# Schematic.net
KiCad netlist of a schematic drawn in EAGLE
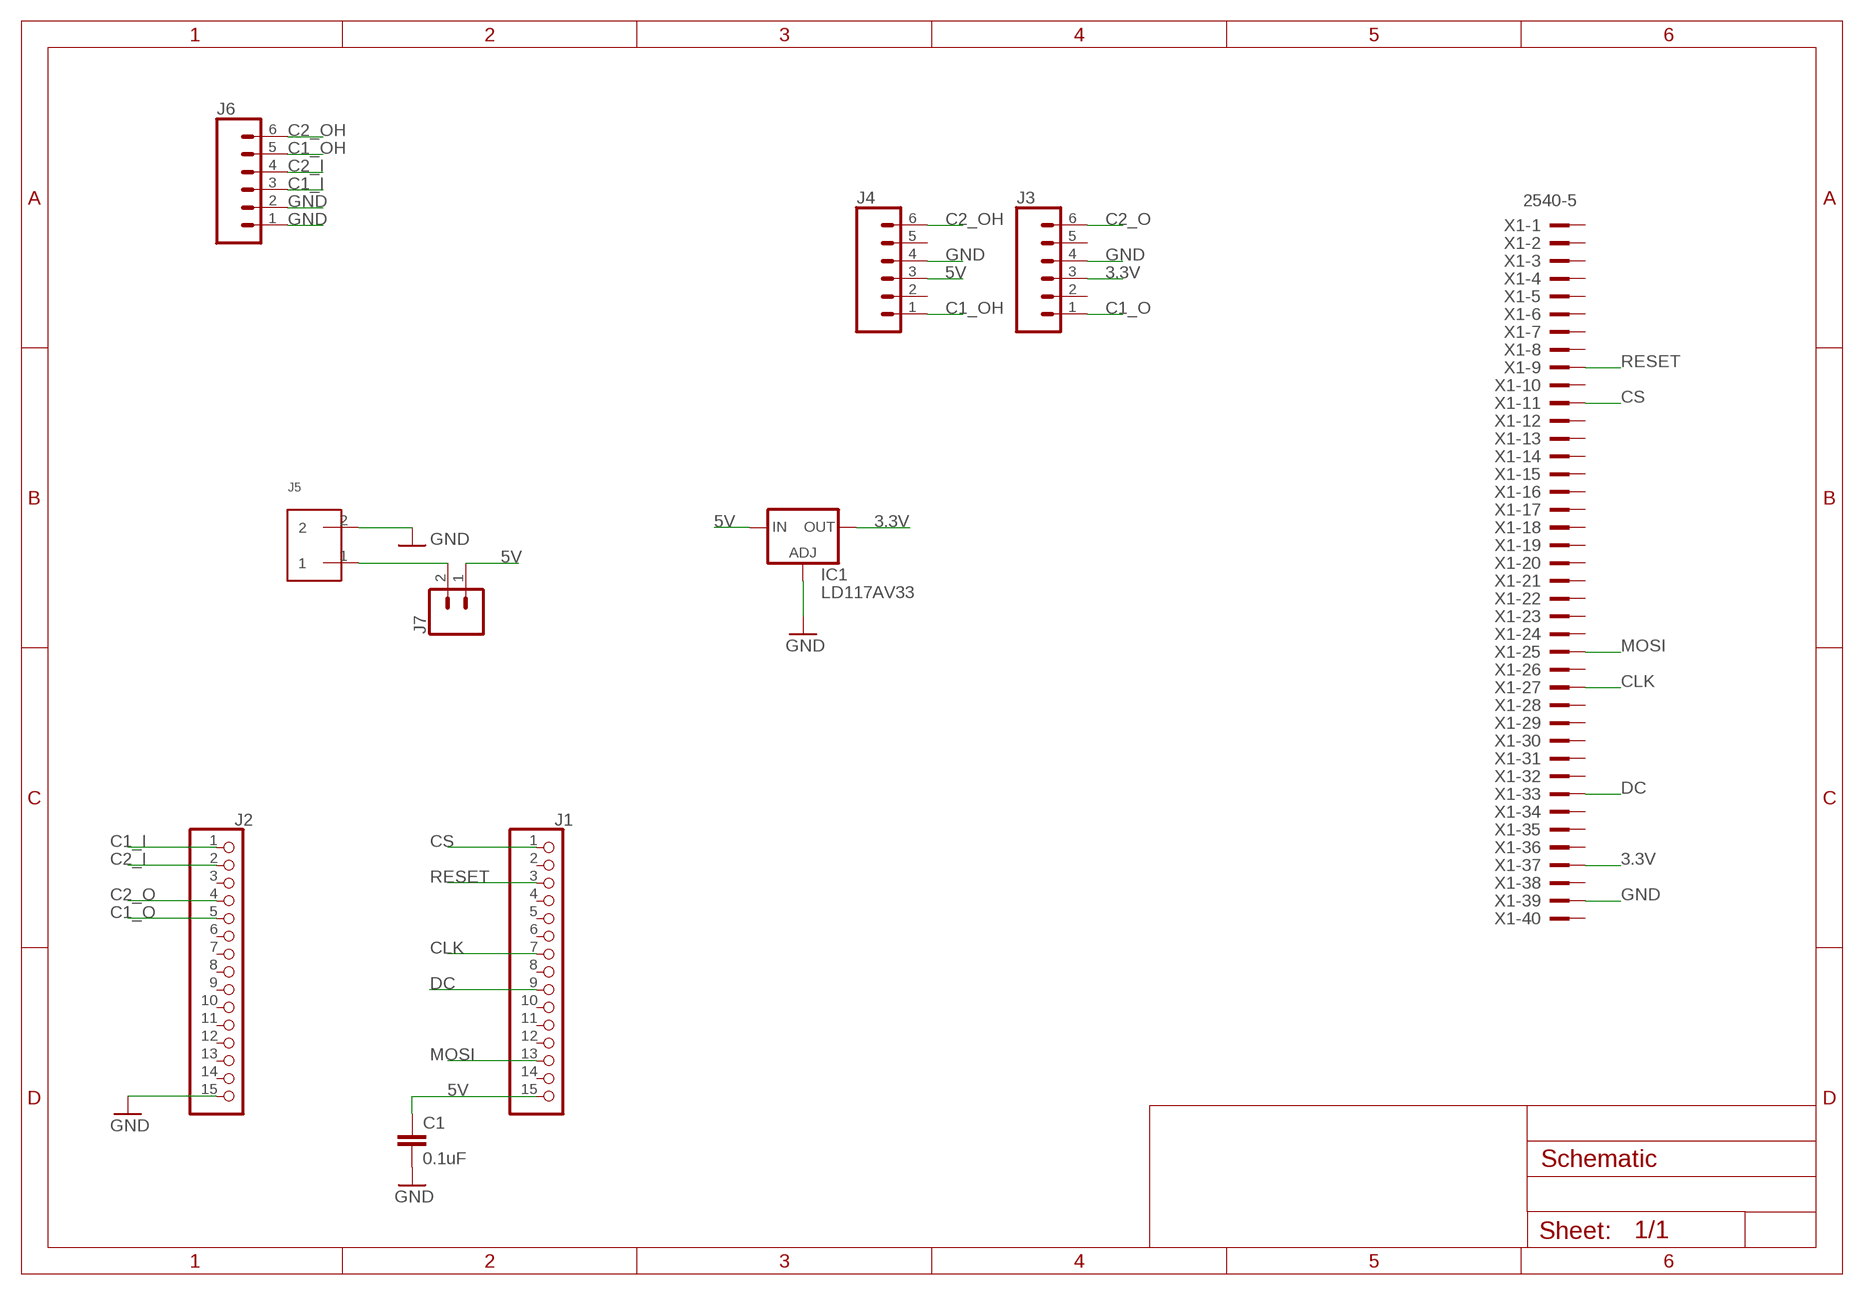
[diagram p0: schematic, sheet 1]

(export (version "E")
  (design (tool "Eeschema 10.0.6"))
  (components
    (comp (ref "C1")
      (value "0.1uF")
      (footprint "eagle-import:CAP-PTH-SMALL-KIT")
      (libsource (lib "eagle-import") (part "0.1UF-KIT-EZ-50V-20%"))
    )
    (comp (ref "IC1")
      (value "LD117AV33")
      (footprint "eagle-import:TO220L1")
      (libsource (lib "eagle-import") (part "LD117A?V33"))
    )
    (comp (ref "J1")
      (value "PINHD-1X15")
      (footprint "eagle-import:1X15")
      (libsource (lib "eagle-import") (part "PINHD-1X15"))
    )
    (comp (ref "J2")
      (value "PINHD-1X15")
      (footprint "eagle-import:1X15")
      (libsource (lib "eagle-import") (part "PINHD-1X15"))
    )
    (comp (ref "J3")
      (value "CONN_06LONGPADS")
      (footprint "eagle-import:1X06_LONGPADS")
      (libsource (lib "eagle-import") (part "CONN_06LONGPADS"))
    )
    (comp (ref "J4")
      (value "CONN_06LONGPADS")
      (footprint "eagle-import:1X06_LONGPADS")
      (libsource (lib "eagle-import") (part "CONN_06LONGPADS"))
    )
    (comp (ref "J5")
      (value "SCREW_TERMINAL")
      (footprint "eagle-import:PHEONIX-1935161")
      (libsource (lib "eagle-import") (part "SCREW_TERMINAL"))
    )
    (comp (ref "J6")
      (value "CONN_06LONGPADS")
      (footprint "eagle-import:1X06_LONGPADS")
      (libsource (lib "eagle-import") (part "CONN_06LONGPADS"))
    )
    (comp (ref "J7")
      (value "CONN_02")
      (footprint "eagle-import:1X02")
      (libsource (lib "eagle-import") (part "CONN_02"))
    )
    (comp (ref "X1")
      (value "2540-5")
      (footprint "eagle-import:PAK100_2500-5-40")
      (libsource (lib "eagle-import") (part "2540-5"))
    )
  )
  (nets
    (net (code "1") (name "/3.3V") (class "Default")
      (node (ref "IC1") (pin "2") (pinfunction "OUT_2") (pintype "passive"))
      (node (ref "J3") (pin "3") (pinfunction "3_3") (pintype "passive"))
      (node (ref "X1") (pin "37") (pinfunction "KL_37") (pintype "passive"))
    )
    (net (code "2") (name "/5V") (class "Default")
      (node (ref "C1") (pin "1") (pinfunction "1_1") (pintype "passive"))
      (node (ref "IC1") (pin "3") (pinfunction "IN_3") (pintype "input"))
      (node (ref "J1") (pin "15") (pinfunction "15_15") (pintype "passive"))
      (node (ref "J4") (pin "3") (pinfunction "3_3") (pintype "passive"))
      (node (ref "J7") (pin "1") (pinfunction "1_1") (pintype "passive"))
    )
    (net (code "3") (name "/C1_I") (class "Default")
      (node (ref "J2") (pin "1") (pinfunction "1_1") (pintype "passive"))
      (node (ref "J6") (pin "3") (pinfunction "3_3") (pintype "passive"))
    )
    (net (code "4") (name "/C1_O") (class "Default")
      (node (ref "J2") (pin "5") (pinfunction "5_5") (pintype "passive"))
      (node (ref "J3") (pin "1") (pinfunction "1_1") (pintype "passive"))
    )
    (net (code "5") (name "/C1_OH") (class "Default")
      (node (ref "J4") (pin "1") (pinfunction "1_1") (pintype "passive"))
      (node (ref "J6") (pin "5") (pinfunction "5_5") (pintype "passive"))
    )
    (net (code "6") (name "/C2_I") (class "Default")
      (node (ref "J2") (pin "2") (pinfunction "2_2") (pintype "passive"))
      (node (ref "J6") (pin "4") (pinfunction "4_4") (pintype "passive"))
    )
    (net (code "7") (name "/C2_O") (class "Default")
      (node (ref "J2") (pin "4") (pinfunction "4_4") (pintype "passive"))
      (node (ref "J3") (pin "6") (pinfunction "6_6") (pintype "passive"))
    )
    (net (code "8") (name "/C2_OH") (class "Default")
      (node (ref "J4") (pin "6") (pinfunction "6_6") (pintype "passive"))
      (node (ref "J6") (pin "6") (pinfunction "6_6") (pintype "passive"))
    )
    (net (code "9") (name "/CLK") (class "Default")
      (node (ref "J1") (pin "7") (pinfunction "7_7") (pintype "passive"))
      (node (ref "X1") (pin "27") (pinfunction "KL_27") (pintype "passive"))
    )
    (net (code "10") (name "/CS") (class "Default")
      (node (ref "J1") (pin "1") (pinfunction "1_1") (pintype "passive"))
      (node (ref "X1") (pin "11") (pinfunction "KL_11") (pintype "passive"))
    )
    (net (code "11") (name "/DC") (class "Default")
      (node (ref "J1") (pin "9") (pinfunction "9_9") (pintype "passive"))
      (node (ref "X1") (pin "33") (pinfunction "KL_33") (pintype "passive"))
    )
    (net (code "12") (name "/MOSI") (class "Default")
      (node (ref "J1") (pin "13") (pinfunction "13_13") (pintype "passive"))
      (node (ref "X1") (pin "25") (pinfunction "KL_25") (pintype "passive"))
    )
    (net (code "13") (name "/RESET") (class "Default")
      (node (ref "J1") (pin "3") (pinfunction "3_3") (pintype "passive"))
      (node (ref "X1") (pin "9") (pinfunction "KL_9") (pintype "passive"))
    )
    (net (code "14") (name "GND") (class "Default")
      (node (ref "C1") (pin "2") (pinfunction "2_2") (pintype "passive"))
      (node (ref "IC1") (pin "1") (pinfunction "ADJ_1") (pintype "input"))
      (node (ref "J2") (pin "15") (pinfunction "15_15") (pintype "passive"))
      (node (ref "J3") (pin "4") (pinfunction "4_4") (pintype "passive"))
      (node (ref "J4") (pin "4") (pinfunction "4_4") (pintype "passive"))
      (node (ref "J5") (pin "2") (pinfunction "2_2") (pintype "bidirectional"))
      (node (ref "J6") (pin "1") (pinfunction "1_1") (pintype "passive"))
      (node (ref "J6") (pin "2") (pinfunction "2_2") (pintype "passive"))
      (node (ref "X1") (pin "39") (pinfunction "KL_39") (pintype "passive"))
    )
    (net (code "15") (name "Net-(J5-Pad1)") (class "Default")
      (node (ref "J5") (pin "1") (pinfunction "1_1") (pintype "bidirectional"))
      (node (ref "J7") (pin "2") (pinfunction "2_2") (pintype "passive"))
    )
    (net (code "16") (name "unconnected-(J1-Pad2)") (class "Default")
      (node (ref "J1") (pin "2") (pinfunction "2_2") (pintype "passive"))
    )
    (net (code "17") (name "unconnected-(J1-Pad4)") (class "Default")
      (node (ref "J1") (pin "4") (pinfunction "4_4") (pintype "passive"))
    )
    (net (code "18") (name "unconnected-(J1-Pad5)") (class "Default")
      (node (ref "J1") (pin "5") (pinfunction "5_5") (pintype "passive"))
    )
    (net (code "19") (name "unconnected-(J1-Pad6)") (class "Default")
      (node (ref "J1") (pin "6") (pinfunction "6_6") (pintype "passive"))
    )
    (net (code "20") (name "unconnected-(J1-Pad8)") (class "Default")
      (node (ref "J1") (pin "8") (pinfunction "8_8") (pintype "passive"))
    )
    (net (code "21") (name "unconnected-(J1-Pad10)") (class "Default")
      (node (ref "J1") (pin "10") (pinfunction "10_10") (pintype "passive"))
    )
    (net (code "22") (name "unconnected-(J1-Pad11)") (class "Default")
      (node (ref "J1") (pin "11") (pinfunction "11_11") (pintype "passive"))
    )
    (net (code "23") (name "unconnected-(J1-Pad12)") (class "Default")
      (node (ref "J1") (pin "12") (pinfunction "12_12") (pintype "passive"))
    )
    (net (code "24") (name "unconnected-(J1-Pad14)") (class "Default")
      (node (ref "J1") (pin "14") (pinfunction "14_14") (pintype "passive"))
    )
    (net (code "25") (name "unconnected-(J2-Pad3)") (class "Default")
      (node (ref "J2") (pin "3") (pinfunction "3_3") (pintype "passive"))
    )
    (net (code "26") (name "unconnected-(J2-Pad6)") (class "Default")
      (node (ref "J2") (pin "6") (pinfunction "6_6") (pintype "passive"))
    )
    (net (code "27") (name "unconnected-(J2-Pad7)") (class "Default")
      (node (ref "J2") (pin "7") (pinfunction "7_7") (pintype "passive"))
    )
    (net (code "28") (name "unconnected-(J2-Pad8)") (class "Default")
      (node (ref "J2") (pin "8") (pinfunction "8_8") (pintype "passive"))
    )
    (net (code "29") (name "unconnected-(J2-Pad9)") (class "Default")
      (node (ref "J2") (pin "9") (pinfunction "9_9") (pintype "passive"))
    )
    (net (code "30") (name "unconnected-(J2-Pad10)") (class "Default")
      (node (ref "J2") (pin "10") (pinfunction "10_10") (pintype "passive"))
    )
    (net (code "31") (name "unconnected-(J2-Pad11)") (class "Default")
      (node (ref "J2") (pin "11") (pinfunction "11_11") (pintype "passive"))
    )
    (net (code "32") (name "unconnected-(J2-Pad12)") (class "Default")
      (node (ref "J2") (pin "12") (pinfunction "12_12") (pintype "passive"))
    )
    (net (code "33") (name "unconnected-(J2-Pad13)") (class "Default")
      (node (ref "J2") (pin "13") (pinfunction "13_13") (pintype "passive"))
    )
    (net (code "34") (name "unconnected-(J2-Pad14)") (class "Default")
      (node (ref "J2") (pin "14") (pinfunction "14_14") (pintype "passive"))
    )
    (net (code "35") (name "unconnected-(J3-Pad2)") (class "Default")
      (node (ref "J3") (pin "2") (pinfunction "2_2") (pintype "passive"))
    )
    (net (code "36") (name "unconnected-(J3-Pad5)") (class "Default")
      (node (ref "J3") (pin "5") (pinfunction "5_5") (pintype "passive"))
    )
    (net (code "37") (name "unconnected-(J4-Pad2)") (class "Default")
      (node (ref "J4") (pin "2") (pinfunction "2_2") (pintype "passive"))
    )
    (net (code "38") (name "unconnected-(J4-Pad5)") (class "Default")
      (node (ref "J4") (pin "5") (pinfunction "5_5") (pintype "passive"))
    )
    (net (code "39") (name "unconnected-(X1A-KL-Pad1)") (class "Default")
      (node (ref "X1") (pin "1") (pinfunction "KL_1") (pintype "passive"))
    )
    (net (code "40") (name "unconnected-(X1AB-KL-Pad34)") (class "Default")
      (node (ref "X1") (pin "34") (pinfunction "KL_34") (pintype "passive"))
    )
    (net (code "41") (name "unconnected-(X1AC-KL-Pad35)") (class "Default")
      (node (ref "X1") (pin "35") (pinfunction "KL_35") (pintype "passive"))
    )
    (net (code "42") (name "unconnected-(X1AD-KL-Pad36)") (class "Default")
      (node (ref "X1") (pin "36") (pinfunction "KL_36") (pintype "passive"))
    )
    (net (code "43") (name "unconnected-(X1AF-KL-Pad38)") (class "Default")
      (node (ref "X1") (pin "38") (pinfunction "KL_38") (pintype "passive"))
    )
    (net (code "44") (name "unconnected-(X1AH-KL-Pad4)") (class "Default")
      (node (ref "X1") (pin "4") (pinfunction "KL_4") (pintype "passive"))
    )
    (net (code "45") (name "unconnected-(X1AI-KL-Pad40)") (class "Default")
      (node (ref "X1") (pin "40") (pinfunction "KL_40") (pintype "passive"))
    )
    (net (code "46") (name "unconnected-(X1AJ-KL-Pad5)") (class "Default")
      (node (ref "X1") (pin "5") (pinfunction "KL_5") (pintype "passive"))
    )
    (net (code "47") (name "unconnected-(X1AK-KL-Pad6)") (class "Default")
      (node (ref "X1") (pin "6") (pinfunction "KL_6") (pintype "passive"))
    )
    (net (code "48") (name "unconnected-(X1AL-KL-Pad7)") (class "Default")
      (node (ref "X1") (pin "7") (pinfunction "KL_7") (pintype "passive"))
    )
    (net (code "49") (name "unconnected-(X1AM-KL-Pad8)") (class "Default")
      (node (ref "X1") (pin "8") (pinfunction "KL_8") (pintype "passive"))
    )
    (net (code "50") (name "unconnected-(X1B-KL-Pad10)") (class "Default")
      (node (ref "X1") (pin "10") (pinfunction "KL_10") (pintype "passive"))
    )
    (net (code "51") (name "unconnected-(X1D-KL-Pad12)") (class "Default")
      (node (ref "X1") (pin "12") (pinfunction "KL_12") (pintype "passive"))
    )
    (net (code "52") (name "unconnected-(X1E-KL-Pad13)") (class "Default")
      (node (ref "X1") (pin "13") (pinfunction "KL_13") (pintype "passive"))
    )
    (net (code "53") (name "unconnected-(X1F-KL-Pad14)") (class "Default")
      (node (ref "X1") (pin "14") (pinfunction "KL_14") (pintype "passive"))
    )
    (net (code "54") (name "unconnected-(X1G-KL-Pad15)") (class "Default")
      (node (ref "X1") (pin "15") (pinfunction "KL_15") (pintype "passive"))
    )
    (net (code "55") (name "unconnected-(X1H-KL-Pad16)") (class "Default")
      (node (ref "X1") (pin "16") (pinfunction "KL_16") (pintype "passive"))
    )
    (net (code "56") (name "unconnected-(X1I-KL-Pad17)") (class "Default")
      (node (ref "X1") (pin "17") (pinfunction "KL_17") (pintype "passive"))
    )
    (net (code "57") (name "unconnected-(X1J-KL-Pad18)") (class "Default")
      (node (ref "X1") (pin "18") (pinfunction "KL_18") (pintype "passive"))
    )
    (net (code "58") (name "unconnected-(X1K-KL-Pad19)") (class "Default")
      (node (ref "X1") (pin "19") (pinfunction "KL_19") (pintype "passive"))
    )
    (net (code "59") (name "unconnected-(X1L-KL-Pad2)") (class "Default")
      (node (ref "X1") (pin "2") (pinfunction "KL_2") (pintype "passive"))
    )
    (net (code "60") (name "unconnected-(X1M-KL-Pad20)") (class "Default")
      (node (ref "X1") (pin "20") (pinfunction "KL_20") (pintype "passive"))
    )
    (net (code "61") (name "unconnected-(X1N-KL-Pad21)") (class "Default")
      (node (ref "X1") (pin "21") (pinfunction "KL_21") (pintype "passive"))
    )
    (net (code "62") (name "unconnected-(X1O-KL-Pad22)") (class "Default")
      (node (ref "X1") (pin "22") (pinfunction "KL_22") (pintype "passive"))
    )
    (net (code "63") (name "unconnected-(X1P-KL-Pad23)") (class "Default")
      (node (ref "X1") (pin "23") (pinfunction "KL_23") (pintype "passive"))
    )
    (net (code "64") (name "unconnected-(X1Q-KL-Pad24)") (class "Default")
      (node (ref "X1") (pin "24") (pinfunction "KL_24") (pintype "passive"))
    )
    (net (code "65") (name "unconnected-(X1S-KL-Pad26)") (class "Default")
      (node (ref "X1") (pin "26") (pinfunction "KL_26") (pintype "passive"))
    )
    (net (code "66") (name "unconnected-(X1U-KL-Pad28)") (class "Default")
      (node (ref "X1") (pin "28") (pinfunction "KL_28") (pintype "passive"))
    )
    (net (code "67") (name "unconnected-(X1V-KL-Pad29)") (class "Default")
      (node (ref "X1") (pin "29") (pinfunction "KL_29") (pintype "passive"))
    )
    (net (code "68") (name "unconnected-(X1W-KL-Pad3)") (class "Default")
      (node (ref "X1") (pin "3") (pinfunction "KL_3") (pintype "passive"))
    )
    (net (code "69") (name "unconnected-(X1X-KL-Pad30)") (class "Default")
      (node (ref "X1") (pin "30") (pinfunction "KL_30") (pintype "passive"))
    )
    (net (code "70") (name "unconnected-(X1Y-KL-Pad31)") (class "Default")
      (node (ref "X1") (pin "31") (pinfunction "KL_31") (pintype "passive"))
    )
    (net (code "71") (name "unconnected-(X1Z-KL-Pad32)") (class "Default")
      (node (ref "X1") (pin "32") (pinfunction "KL_32") (pintype "passive"))
    )
  )
)
